# Battery_Front_End.net
KiCad netlist of a schematic drawn in Altium Designer
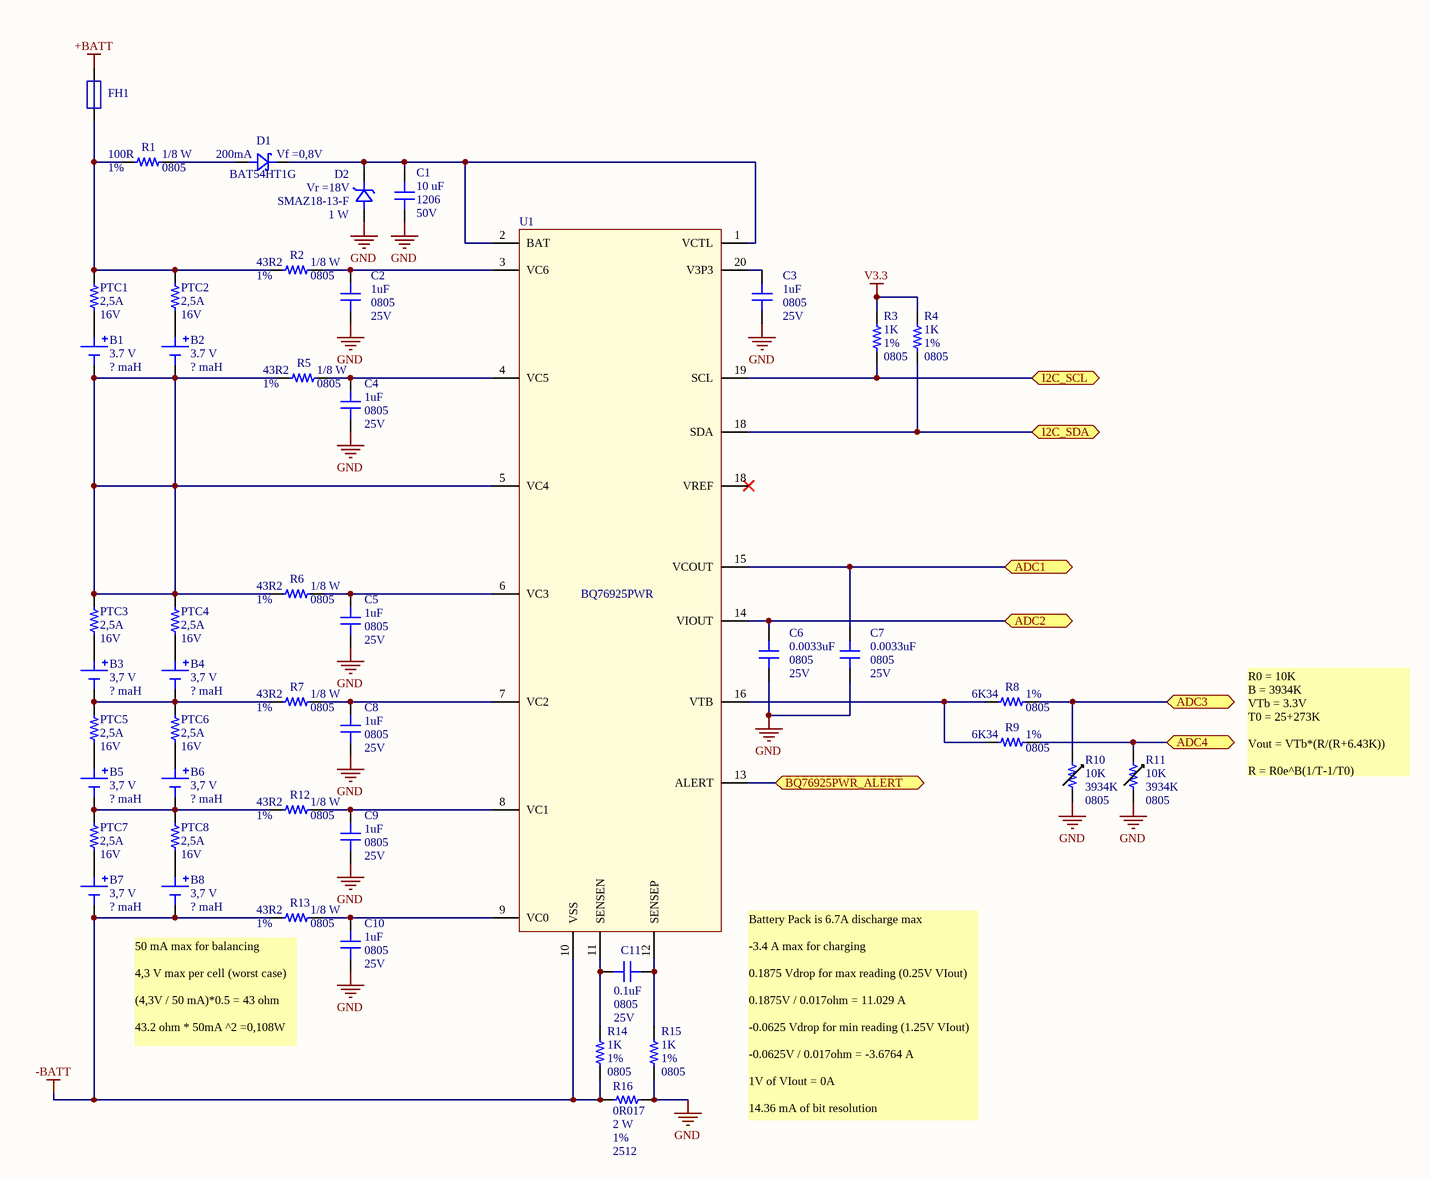
[diagram p0: Battery Front End.SchDoc]

(export (version "E")
  (design (tool "Eeschema 10.0.6"))
  (components
    (comp (ref "B1")
      (value "Battery Cell 18650")
      (footprint "18650 PC PIN")
      (fields
        (field (name "PART NUMBER") "36-54-ND")
        (field (name "VOLTAGE") "3.7 V")
        (field (name "CHARGE") "? maH")
      )
      (libsource (lib "SecureBot") (part "Battery Cell 18650"))
    )
    (comp (ref "B2")
      (value "Battery Cell 18650")
      (footprint "18650 PC PIN")
      (fields
        (field (name "PART NUMBER") "36-54-ND")
        (field (name "VOLTAGE") "3.7 V")
        (field (name "CHARGE") "? maH")
      )
      (libsource (lib "SecureBot") (part "Battery Cell 18650"))
    )
    (comp (ref "B3")
      (value "Battery Cell 18650")
      (footprint "18650 PC PIN")
      (fields
        (field (name "PART NUMBER") "36-54-ND")
        (field (name "VOLTAGE") "3,7 V")
        (field (name "CHARGE") "? maH")
      )
      (libsource (lib "SecureBot") (part "Battery Cell 18650"))
    )
    (comp (ref "B4")
      (value "Battery Cell 18650")
      (footprint "18650 PC PIN")
      (fields
        (field (name "PART NUMBER") "36-54-ND")
        (field (name "VOLTAGE") "3,7 V")
        (field (name "CHARGE") "? maH")
      )
      (libsource (lib "SecureBot") (part "Battery Cell 18650"))
    )
    (comp (ref "B5")
      (value "Battery Cell 18650")
      (footprint "18650 PC PIN")
      (fields
        (field (name "PART NUMBER") "36-54-ND")
        (field (name "VOLTAGE") "3,7 V")
        (field (name "CHARGE") "? maH")
      )
      (libsource (lib "SecureBot") (part "Battery Cell 18650"))
    )
    (comp (ref "B6")
      (value "Battery Cell 18650")
      (footprint "18650 PC PIN")
      (fields
        (field (name "PART NUMBER") "36-54-ND")
        (field (name "VOLTAGE") "3,7 V")
        (field (name "CHARGE") "? maH")
      )
      (libsource (lib "SecureBot") (part "Battery Cell 18650"))
    )
    (comp (ref "B7")
      (value "Battery Cell 18650")
      (footprint "18650 PC PIN")
      (fields
        (field (name "PART NUMBER") "36-54-ND")
        (field (name "VOLTAGE") "3,7 V")
        (field (name "CHARGE") "? maH")
      )
      (libsource (lib "SecureBot") (part "Battery Cell 18650"))
    )
    (comp (ref "B8")
      (value "Battery Cell 18650")
      (footprint "18650 PC PIN")
      (fields
        (field (name "PART NUMBER") "36-54-ND")
        (field (name "VOLTAGE") "3,7 V")
        (field (name "CHARGE") "? maH")
      )
      (libsource (lib "SecureBot") (part "Battery Cell 18650"))
    )
    (comp (ref "C1")
      (value "10 uF")
      (footprint "CAP_1206")
      (description "CAP - 1206")
      (fields
        (field (name "PACKAGE") "1206")
        (field (name "VOLTAGE") "50V")
        (field (name "PART NUMBER") "GRT31CR61H106ME01L")
      )
      (libsource (lib "SecureBot") (part "CAP - 1206"))
    )
    (comp (ref "C2")
      (value "1uF")
      (footprint "CAP_0805")
      (description "CAP - 0805")
      (fields
        (field (name "PART NUMBER") "CL21B105KAFNNNE")
        (field (name "PACKAGE") "0805")
        (field (name "VOLTAGE") "25V")
      )
      (libsource (lib "SecureBot") (part "CAP - 0805"))
    )
    (comp (ref "C3")
      (value "1uF")
      (footprint "CAP_0805")
      (description "CAP - 0805")
      (fields
        (field (name "PART NUMBER") "CL21B105KAFNNNE")
        (field (name "PACKAGE") "0805")
        (field (name "VOLTAGE") "25V")
      )
      (libsource (lib "SecureBot") (part "CAP - 0805"))
    )
    (comp (ref "C4")
      (value "1uF")
      (footprint "CAP_0805")
      (description "CAP - 0805")
      (fields
        (field (name "PART NUMBER") "CL21B105KAFNNNE")
        (field (name "PACKAGE") "0805")
        (field (name "VOLTAGE") "25V")
      )
      (libsource (lib "SecureBot") (part "CAP - 0805"))
    )
    (comp (ref "C5")
      (value "1uF")
      (footprint "CAP_0805")
      (description "CAP - 0805")
      (fields
        (field (name "PART NUMBER") "CL21B105KAFNNNE")
        (field (name "PACKAGE") "0805")
        (field (name "VOLTAGE") "25V")
      )
      (libsource (lib "SecureBot") (part "CAP - 0805"))
    )
    (comp (ref "C6")
      (value "0.0033uF")
      (footprint "CAP_0805")
      (description "CAP - 0805")
      (fields
        (field (name "PART NUMBER") "CL21B332KBANNNC")
        (field (name "PACKAGE") "0805")
        (field (name "VOLTAGE") "25V")
      )
      (libsource (lib "SecureBot") (part "CAP - 0805"))
    )
    (comp (ref "C7")
      (value "0.0033uF")
      (footprint "CAP_0805")
      (description "CAP - 0805")
      (fields
        (field (name "PART NUMBER") "CL21B332KBANNNC")
        (field (name "PACKAGE") "0805")
        (field (name "VOLTAGE") "25V")
      )
      (libsource (lib "SecureBot") (part "CAP - 0805"))
    )
    (comp (ref "C8")
      (value "1uF")
      (footprint "CAP_0805")
      (description "CAP - 0805")
      (fields
        (field (name "PART NUMBER") "CL21B105KAFNNNE")
        (field (name "PACKAGE") "0805")
        (field (name "VOLTAGE") "25V")
      )
      (libsource (lib "SecureBot") (part "CAP - 0805"))
    )
    (comp (ref "C9")
      (value "1uF")
      (footprint "CAP_0805")
      (description "CAP - 0805")
      (fields
        (field (name "PART NUMBER") "CL21B105KAFNNNE")
        (field (name "PACKAGE") "0805")
        (field (name "VOLTAGE") "25V")
      )
      (libsource (lib "SecureBot") (part "CAP - 0805"))
    )
    (comp (ref "C10")
      (value "1uF")
      (footprint "CAP_0805")
      (description "CAP - 0805")
      (fields
        (field (name "PART NUMBER") "CL21B105KAFNNNE")
        (field (name "PACKAGE") "0805")
        (field (name "VOLTAGE") "25V")
      )
      (libsource (lib "SecureBot") (part "CAP - 0805"))
    )
    (comp (ref "C11")
      (value "0.1uF")
      (footprint "CAP_0805")
      (description "CAP - 0805")
      (fields
        (field (name "PART NUMBER") "CC0805KRX7R8BB104")
        (field (name "PACKAGE") "0805")
        (field (name "VOLTAGE") "25V")
      )
      (libsource (lib "SecureBot") (part "CAP - 0805"))
    )
    (comp (ref "D1")
      (value "SCHOTTKEY")
      (footprint "SOD-323")
      (fields
        (field (name "CURRENT") "200mA")
        (field (name "VF") "Vf =0,8V")
        (field (name "PART NUMBER") "BAT54HT1G")
      )
      (libsource (lib "SecureBot") (part "SCHOTTKEY"))
    )
    (comp (ref "D2")
      (value "DIODE ZENER")
      (footprint "DO-214AC_SOD128")
      (fields
        (field (name "VF") "Vr =18V")
        (field (name "PART NUMBER") "SMAZ18-13-F")
        (field (name "POWER") "1 W")
      )
      (libsource (lib "SecureBot") (part "DIODE ZENER"))
    )
    (comp (ref "FH1")
      (value "FH 3AB-3AG")
      (footprint "FH_3AB_3AG")
      (description "Fuse holder (3AB-3AG)")
      (fields (field (name "PART NUMBER") "01020071Z x2"))
      (libsource (lib "SecureBot") (part "FH 3AB-3AG"))
    )
    (comp (ref "PTC1")
      (value "PTC - 1812")
      (footprint "PTC - 1812")
      (fields
        (field (name "PART NUMBER") "0ZCG0160BF2C")
        (field (name "TRIP VALUE") "2,5A")
        (field (name "VOLTAGE") "16V")
      )
      (libsource (lib "SecureBot") (part "PTC - 1812"))
    )
    (comp (ref "PTC2")
      (value "PTC - 1812")
      (footprint "PTC - 1812")
      (fields
        (field (name "PART NUMBER") "0ZCG0160BF2C")
        (field (name "TRIP VALUE") "2,5A")
        (field (name "VOLTAGE") "16V")
      )
      (libsource (lib "SecureBot") (part "PTC - 1812"))
    )
    (comp (ref "PTC3")
      (value "PTC - 1812")
      (footprint "PTC - 1812")
      (fields
        (field (name "PART NUMBER") "0ZCG0160BF2C")
        (field (name "TRIP VALUE") "2,5A")
        (field (name "VOLTAGE") "16V")
      )
      (libsource (lib "SecureBot") (part "PTC - 1812"))
    )
    (comp (ref "PTC4")
      (value "PTC - 1812")
      (footprint "PTC - 1812")
      (fields
        (field (name "PART NUMBER") "0ZCG0160BF2C")
        (field (name "TRIP VALUE") "2,5A")
        (field (name "VOLTAGE") "16V")
      )
      (libsource (lib "SecureBot") (part "PTC - 1812"))
    )
    (comp (ref "PTC5")
      (value "PTC - 1812")
      (footprint "PTC - 1812")
      (fields
        (field (name "PART NUMBER") "0ZCG0160BF2C")
        (field (name "TRIP VALUE") "2,5A")
        (field (name "VOLTAGE") "16V")
      )
      (libsource (lib "SecureBot") (part "PTC - 1812"))
    )
    (comp (ref "PTC6")
      (value "PTC - 1812")
      (footprint "PTC - 1812")
      (fields
        (field (name "PART NUMBER") "0ZCG0160BF2C")
        (field (name "TRIP VALUE") "2,5A")
        (field (name "VOLTAGE") "16V")
      )
      (libsource (lib "SecureBot") (part "PTC - 1812"))
    )
    (comp (ref "PTC7")
      (value "PTC - 1812")
      (footprint "PTC - 1812")
      (fields
        (field (name "PART NUMBER") "0ZCG0160BF2C")
        (field (name "TRIP VALUE") "2,5A")
        (field (name "VOLTAGE") "16V")
      )
      (libsource (lib "SecureBot") (part "PTC - 1812"))
    )
    (comp (ref "PTC8")
      (value "PTC - 1812")
      (footprint "PTC - 1812")
      (fields
        (field (name "PART NUMBER") "0ZCG0160BF2C")
        (field (name "TRIP VALUE") "2,5A")
        (field (name "VOLTAGE") "16V")
      )
      (libsource (lib "SecureBot") (part "PTC - 1812"))
    )
    (comp (ref "R1")
      (value "100R")
      (footprint "RES_0805")
      (description "RES - 0805")
      (fields
        (field (name "PART NUMBER") "ERA-6AEB101V")
        (field (name "WATT") "1/8 W")
        (field (name "TOLERANCE") "1%")
        (field (name "PACKAGE") "0805")
      )
      (libsource (lib "SecureBot") (part "RES - 0805"))
    )
    (comp (ref "R2")
      (value "43R2")
      (footprint "RES_0805")
      (description "RES - 0805")
      (fields
        (field (name "PART NUMBER") "ERJ-6ENF43R2V")
        (field (name "WATT") "1/8 W")
        (field (name "TOLERANCE") "1%")
        (field (name "PACKAGE") "0805")
      )
      (libsource (lib "SecureBot") (part "RES - 0805"))
    )
    (comp (ref "R3")
      (value "1K")
      (footprint "RES_0805")
      (description "RES - 0805")
      (fields
        (field (name "PART NUMBER") "RNCP0805FTD1K00")
        (field (name "TOLERANCE") "1%")
        (field (name "PACKAGE") "0805")
      )
      (libsource (lib "SecureBot") (part "RES - 0805"))
    )
    (comp (ref "R4")
      (value "1K")
      (footprint "RES_0805")
      (description "RES - 0805")
      (fields
        (field (name "PART NUMBER") "RNCP0805FTD1K00")
        (field (name "TOLERANCE") "1%")
        (field (name "PACKAGE") "0805")
      )
      (libsource (lib "SecureBot") (part "RES - 0805"))
    )
    (comp (ref "R5")
      (value "43R2")
      (footprint "RES_0805")
      (description "RES - 0805")
      (fields
        (field (name "PART NUMBER") "ERJ-6ENF43R2V")
        (field (name "WATT") "1/8 W")
        (field (name "TOLERANCE") "1%")
        (field (name "PACKAGE") "0805")
      )
      (libsource (lib "SecureBot") (part "RES - 0805"))
    )
    (comp (ref "R6")
      (value "43R2")
      (footprint "RES_0805")
      (description "RES - 0805")
      (fields
        (field (name "PART NUMBER") "ERJ-6ENF43R2V")
        (field (name "WATT") "1/8 W")
        (field (name "TOLERANCE") "1%")
        (field (name "PACKAGE") "0805")
      )
      (libsource (lib "SecureBot") (part "RES - 0805"))
    )
    (comp (ref "R7")
      (value "43R2")
      (footprint "RES_0805")
      (description "RES - 0805")
      (fields
        (field (name "PART NUMBER") "ERJ-6ENF43R2V")
        (field (name "WATT") "1/8 W")
        (field (name "TOLERANCE") "1%")
        (field (name "PACKAGE") "0805")
      )
      (libsource (lib "SecureBot") (part "RES - 0805"))
    )
    (comp (ref "R8")
      (value "6K34")
      (footprint "RES_0805")
      (description "RES - 0805")
      (fields
        (field (name "PART NUMBER") "CRCW08056K34FKEA")
        (field (name "TOLERANCE") "1%")
        (field (name "PACKAGE") "0805")
      )
      (libsource (lib "SecureBot") (part "RES - 0805"))
    )
    (comp (ref "R9")
      (value "6K34")
      (footprint "RES_0805")
      (description "RES - 0805")
      (fields
        (field (name "PART NUMBER") "CRCW08056K34FKEA")
        (field (name "TOLERANCE") "1%")
        (field (name "PACKAGE") "0805")
      )
      (libsource (lib "SecureBot") (part "RES - 0805"))
    )
    (comp (ref "R10")
      (value "TH - 0805")
      (footprint "RES_0805")
      (fields
        (field (name "PART NUMBER") "NCP21XV103J03RA")
        (field (name "RESISTANCE @ 25C") "10K")
        (field (name "B") "3934K")
        (field (name "PACKAGE") "0805")
      )
      (libsource (lib "SecureBot") (part "TH - 0805"))
    )
    (comp (ref "R11")
      (value "TH - 0805")
      (footprint "RES_0805")
      (fields
        (field (name "PART NUMBER") "NCP21XV103J03RA")
        (field (name "RESISTANCE @ 25C") "10K")
        (field (name "B") "3934K")
        (field (name "PACKAGE") "0805")
      )
      (libsource (lib "SecureBot") (part "TH - 0805"))
    )
    (comp (ref "R12")
      (value "43R2")
      (footprint "RES_0805")
      (description "RES - 0805")
      (fields
        (field (name "PART NUMBER") "ERJ-6ENF43R2V")
        (field (name "WATT") "1/8 W")
        (field (name "TOLERANCE") "1%")
        (field (name "PACKAGE") "0805")
      )
      (libsource (lib "SecureBot") (part "RES - 0805"))
    )
    (comp (ref "R13")
      (value "43R2")
      (footprint "RES_0805")
      (description "RES - 0805")
      (fields
        (field (name "PART NUMBER") "ERJ-6ENF43R2V")
        (field (name "WATT") "1/8 W")
        (field (name "TOLERANCE") "1%")
        (field (name "PACKAGE") "0805")
      )
      (libsource (lib "SecureBot") (part "RES - 0805"))
    )
    (comp (ref "R14")
      (value "1K")
      (footprint "RES_0805")
      (description "RES - 0805")
      (fields
        (field (name "PART NUMBER") "RNCP0805FTD1K00")
        (field (name "TOLERANCE") "1%")
        (field (name "PACKAGE") "0805")
      )
      (libsource (lib "SecureBot") (part "RES - 0805"))
    )
    (comp (ref "R15")
      (value "1K")
      (footprint "RES_0805")
      (description "RES - 0805")
      (fields
        (field (name "PART NUMBER") "RNCP0805FTD1K00")
        (field (name "TOLERANCE") "1%")
        (field (name "PACKAGE") "0805")
      )
      (libsource (lib "SecureBot") (part "RES - 0805"))
    )
    (comp (ref "R16")
      (value "0R017")
      (footprint "RES_2512")
      (description "RES - 2512")
      (fields
        (field (name "PART NUMBER") "WSL2512R0170FEA18")
        (field (name "WATT") "2 W")
        (field (name "TOLERANCE") "1%")
        (field (name "PACKAGE") "2512")
      )
      (libsource (lib "SecureBot") (part "RES - 2512"))
    )
    (comp (ref "U1")
      (value "BQ76925PWR")
      (footprint "BQ76925")
      (libsource (lib "SecureBot") (part "BQ76925PWR"))
    )
  )
  (nets
    (net (code "1") (name "+BATT") (class "Default")
      (node (ref "FH1") (pin "2") (pinfunction "2_2") (pintype "passive"))
    )
    (net (code "2") (name "-BATT") (class "Default")
      (node (ref "B7") (pin "2") (pinfunction "2_2") (pintype "passive"))
      (node (ref "B8") (pin "2") (pinfunction "2_2") (pintype "passive"))
      (node (ref "R13") (pin "1") (pinfunction "1_1") (pintype "passive"))
      (node (ref "R14") (pin "1") (pinfunction "1_1") (pintype "passive"))
      (node (ref "R16") (pin "1") (pinfunction "1_1") (pintype "passive"))
      (node (ref "U1") (pin "10") (pinfunction "VSS_10") (pintype "passive"))
    )
    (net (code "3") (name "/ADC1") (class "Default")
      (node (ref "C7") (pin "1") (pinfunction "1_1") (pintype "passive"))
      (node (ref "U1") (pin "15") (pinfunction "VCOUT_15") (pintype "passive"))
    )
    (net (code "4") (name "/ADC2") (class "Default")
      (node (ref "C6") (pin "1") (pinfunction "1_1") (pintype "passive"))
      (node (ref "U1") (pin "14") (pinfunction "VIOUT_14") (pintype "passive"))
    )
    (net (code "5") (name "/ADC3") (class "Default")
      (node (ref "R10") (pin "1") (pinfunction "1_1") (pintype "passive"))
      (node (ref "R8") (pin "1") (pinfunction "1_1") (pintype "passive"))
    )
    (net (code "6") (name "/ADC4") (class "Default")
      (node (ref "R11") (pin "1") (pinfunction "1_1") (pintype "passive"))
      (node (ref "R9") (pin "1") (pinfunction "1_1") (pintype "passive"))
    )
    (net (code "7") (name "/BQ76925PWR_ALERT") (class "Default")
      (node (ref "U1") (pin "13") (pinfunction "ALERT_13") (pintype "passive"))
    )
    (net (code "8") (name "/I2C_SCL") (class "Default")
      (node (ref "R3") (pin "1") (pinfunction "1_1") (pintype "passive"))
      (node (ref "U1") (pin "19") (pinfunction "SCL_19") (pintype "passive"))
    )
    (net (code "9") (name "/I2C_SDA") (class "Default")
      (node (ref "R4") (pin "1") (pinfunction "1_1") (pintype "passive"))
      (node (ref "U1") (pin "18") (pinfunction "SDA_18") (pintype "passive"))
    )
    (net (code "10") (name "GND") (class "Default")
      (node (ref "C1") (pin "2") (pinfunction "2_2") (pintype "passive"))
      (node (ref "C10") (pin "2") (pinfunction "2_2") (pintype "passive"))
      (node (ref "C2") (pin "2") (pinfunction "2_2") (pintype "passive"))
      (node (ref "C3") (pin "2") (pinfunction "2_2") (pintype "passive"))
      (node (ref "C4") (pin "2") (pinfunction "2_2") (pintype "passive"))
      (node (ref "C5") (pin "2") (pinfunction "2_2") (pintype "passive"))
      (node (ref "C6") (pin "2") (pinfunction "2_2") (pintype "passive"))
      (node (ref "C7") (pin "2") (pinfunction "2_2") (pintype "passive"))
      (node (ref "C8") (pin "2") (pinfunction "2_2") (pintype "passive"))
      (node (ref "C9") (pin "2") (pinfunction "2_2") (pintype "passive"))
      (node (ref "D2") (pin "1") (pinfunction "1_1") (pintype "passive"))
      (node (ref "R10") (pin "2") (pinfunction "2_2") (pintype "passive"))
      (node (ref "R11") (pin "2") (pinfunction "2_2") (pintype "passive"))
      (node (ref "R15") (pin "1") (pinfunction "1_1") (pintype "passive"))
      (node (ref "R16") (pin "2") (pinfunction "2_2") (pintype "passive"))
    )
    (net (code "11") (name "Net-(B1-Pad1)") (class "Default")
      (node (ref "B1") (pin "1") (pinfunction "1_1") (pintype "passive"))
      (node (ref "PTC1") (pin "2") (pinfunction "2_2") (pintype "passive"))
    )
    (net (code "12") (name "Net-(B2-Pad1)") (class "Default")
      (node (ref "B2") (pin "1") (pinfunction "1_1") (pintype "passive"))
      (node (ref "PTC2") (pin "2") (pinfunction "2_2") (pintype "passive"))
    )
    (net (code "13") (name "Net-(B3-Pad1)") (class "Default")
      (node (ref "B3") (pin "1") (pinfunction "1_1") (pintype "passive"))
      (node (ref "PTC3") (pin "2") (pinfunction "2_2") (pintype "passive"))
    )
    (net (code "14") (name "Net-(B3-Pad2)") (class "Default")
      (node (ref "B3") (pin "2") (pinfunction "2_2") (pintype "passive"))
      (node (ref "B4") (pin "2") (pinfunction "2_2") (pintype "passive"))
      (node (ref "PTC5") (pin "1") (pinfunction "1_1") (pintype "passive"))
      (node (ref "PTC6") (pin "1") (pinfunction "1_1") (pintype "passive"))
      (node (ref "R7") (pin "1") (pinfunction "1_1") (pintype "passive"))
    )
    (net (code "15") (name "Net-(B4-Pad1)") (class "Default")
      (node (ref "B4") (pin "1") (pinfunction "1_1") (pintype "passive"))
      (node (ref "PTC4") (pin "2") (pinfunction "2_2") (pintype "passive"))
    )
    (net (code "16") (name "Net-(B5-Pad1)") (class "Default")
      (node (ref "B5") (pin "1") (pinfunction "1_1") (pintype "passive"))
      (node (ref "PTC5") (pin "2") (pinfunction "2_2") (pintype "passive"))
    )
    (net (code "17") (name "Net-(B5-Pad2)") (class "Default")
      (node (ref "B5") (pin "2") (pinfunction "2_2") (pintype "passive"))
      (node (ref "B6") (pin "2") (pinfunction "2_2") (pintype "passive"))
      (node (ref "PTC7") (pin "1") (pinfunction "1_1") (pintype "passive"))
      (node (ref "PTC8") (pin "1") (pinfunction "1_1") (pintype "passive"))
      (node (ref "R12") (pin "1") (pinfunction "1_1") (pintype "passive"))
    )
    (net (code "18") (name "Net-(B6-Pad1)") (class "Default")
      (node (ref "B6") (pin "1") (pinfunction "1_1") (pintype "passive"))
      (node (ref "PTC6") (pin "2") (pinfunction "2_2") (pintype "passive"))
    )
    (net (code "19") (name "Net-(B7-Pad1)") (class "Default")
      (node (ref "B7") (pin "1") (pinfunction "1_1") (pintype "passive"))
      (node (ref "PTC7") (pin "2") (pinfunction "2_2") (pintype "passive"))
    )
    (net (code "20") (name "Net-(B8-Pad1)") (class "Default")
      (node (ref "B8") (pin "1") (pinfunction "1_1") (pintype "passive"))
      (node (ref "PTC8") (pin "2") (pinfunction "2_2") (pintype "passive"))
    )
    (net (code "21") (name "Net-(D1-Pad1)") (class "Default")
      (node (ref "D1") (pin "1") (pinfunction "1_1") (pintype "passive"))
      (node (ref "R1") (pin "2") (pinfunction "2_2") (pintype "passive"))
    )
    (net (code "22") (name "Net-(FH1-Pad1)") (class "Default")
      (node (ref "FH1") (pin "1") (pinfunction "1_1") (pintype "passive"))
      (node (ref "PTC1") (pin "1") (pinfunction "1_1") (pintype "passive"))
      (node (ref "PTC2") (pin "1") (pinfunction "1_1") (pintype "passive"))
      (node (ref "R1") (pin "1") (pinfunction "1_1") (pintype "passive"))
      (node (ref "R2") (pin "1") (pinfunction "1_1") (pintype "passive"))
    )
    (net (code "23") (name "Net-(U1-BAT)") (class "Default")
      (node (ref "C1") (pin "1") (pinfunction "1_1") (pintype "passive"))
      (node (ref "D1") (pin "2") (pinfunction "2_2") (pintype "passive"))
      (node (ref "D2") (pin "2") (pinfunction "2_2") (pintype "passive"))
      (node (ref "U1") (pin "1") (pinfunction "VCTL_1") (pintype "passive"))
      (node (ref "U1") (pin "2") (pinfunction "BAT_2") (pintype "passive"))
    )
    (net (code "24") (name "Net-(U1-SENSEN)") (class "Default")
      (node (ref "C11") (pin "1") (pinfunction "1_1") (pintype "passive"))
      (node (ref "R14") (pin "2") (pinfunction "2_2") (pintype "passive"))
      (node (ref "U1") (pin "11") (pinfunction "SENSEN_11") (pintype "passive"))
    )
    (net (code "25") (name "Net-(U1-SENSEP)") (class "Default")
      (node (ref "C11") (pin "2") (pinfunction "2_2") (pintype "passive"))
      (node (ref "R15") (pin "2") (pinfunction "2_2") (pintype "passive"))
      (node (ref "U1") (pin "12") (pinfunction "SENSEP_12") (pintype "passive"))
    )
    (net (code "26") (name "Net-(U1-V3P3)") (class "Default")
      (node (ref "C3") (pin "1") (pinfunction "1_1") (pintype "passive"))
      (node (ref "U1") (pin "20") (pinfunction "V3P3_20") (pintype "passive"))
    )
    (net (code "27") (name "Net-(U1-VC0)") (class "Default")
      (node (ref "C10") (pin "1") (pinfunction "1_1") (pintype "passive"))
      (node (ref "R13") (pin "2") (pinfunction "2_2") (pintype "passive"))
      (node (ref "U1") (pin "9") (pinfunction "VC0_9") (pintype "passive"))
    )
    (net (code "28") (name "Net-(U1-VC1)") (class "Default")
      (node (ref "C9") (pin "1") (pinfunction "1_1") (pintype "passive"))
      (node (ref "R12") (pin "2") (pinfunction "2_2") (pintype "passive"))
      (node (ref "U1") (pin "8") (pinfunction "VC1_8") (pintype "passive"))
    )
    (net (code "29") (name "Net-(U1-VC2)") (class "Default")
      (node (ref "C8") (pin "1") (pinfunction "1_1") (pintype "passive"))
      (node (ref "R7") (pin "2") (pinfunction "2_2") (pintype "passive"))
      (node (ref "U1") (pin "7") (pinfunction "VC2_7") (pintype "passive"))
    )
    (net (code "30") (name "Net-(U1-VC3)") (class "Default")
      (node (ref "C5") (pin "1") (pinfunction "1_1") (pintype "passive"))
      (node (ref "R6") (pin "2") (pinfunction "2_2") (pintype "passive"))
      (node (ref "U1") (pin "6") (pinfunction "VC3_6") (pintype "passive"))
    )
    (net (code "31") (name "Net-(U1-VC4)") (class "Default")
      (node (ref "B1") (pin "2") (pinfunction "2_2") (pintype "passive"))
      (node (ref "B2") (pin "2") (pinfunction "2_2") (pintype "passive"))
      (node (ref "PTC3") (pin "1") (pinfunction "1_1") (pintype "passive"))
      (node (ref "PTC4") (pin "1") (pinfunction "1_1") (pintype "passive"))
      (node (ref "R5") (pin "1") (pinfunction "1_1") (pintype "passive"))
      (node (ref "R6") (pin "1") (pinfunction "1_1") (pintype "passive"))
      (node (ref "U1") (pin "5") (pinfunction "VC4_5") (pintype "passive"))
    )
    (net (code "32") (name "Net-(U1-VC5)") (class "Default")
      (node (ref "C4") (pin "1") (pinfunction "1_1") (pintype "passive"))
      (node (ref "R5") (pin "2") (pinfunction "2_2") (pintype "passive"))
      (node (ref "U1") (pin "4") (pinfunction "VC5_4") (pintype "passive"))
    )
    (net (code "33") (name "Net-(U1-VC6)") (class "Default")
      (node (ref "C2") (pin "1") (pinfunction "1_1") (pintype "passive"))
      (node (ref "R2") (pin "2") (pinfunction "2_2") (pintype "passive"))
      (node (ref "U1") (pin "3") (pinfunction "VC6_3") (pintype "passive"))
    )
    (net (code "34") (name "Net-(U1-VTB)") (class "Default")
      (node (ref "R8") (pin "2") (pinfunction "2_2") (pintype "passive"))
      (node (ref "R9") (pin "2") (pinfunction "2_2") (pintype "passive"))
      (node (ref "U1") (pin "16") (pinfunction "VTB_16") (pintype "passive"))
    )
    (net (code "35") (name "V3.3") (class "Default")
      (node (ref "R3") (pin "2") (pinfunction "2_2") (pintype "passive"))
      (node (ref "R4") (pin "2") (pinfunction "2_2") (pintype "passive"))
    )
    (net (code "36") (name "unconnected-(U1-VREF-Pad18)") (class "Default")
      (node (ref "U1") (pin "18") (pinfunction "VREF_18") (pintype "passive+no_connect"))
    )
  )
)
